# Sensor.net
KiCad netlist of a schematic drawn in Altium Designer
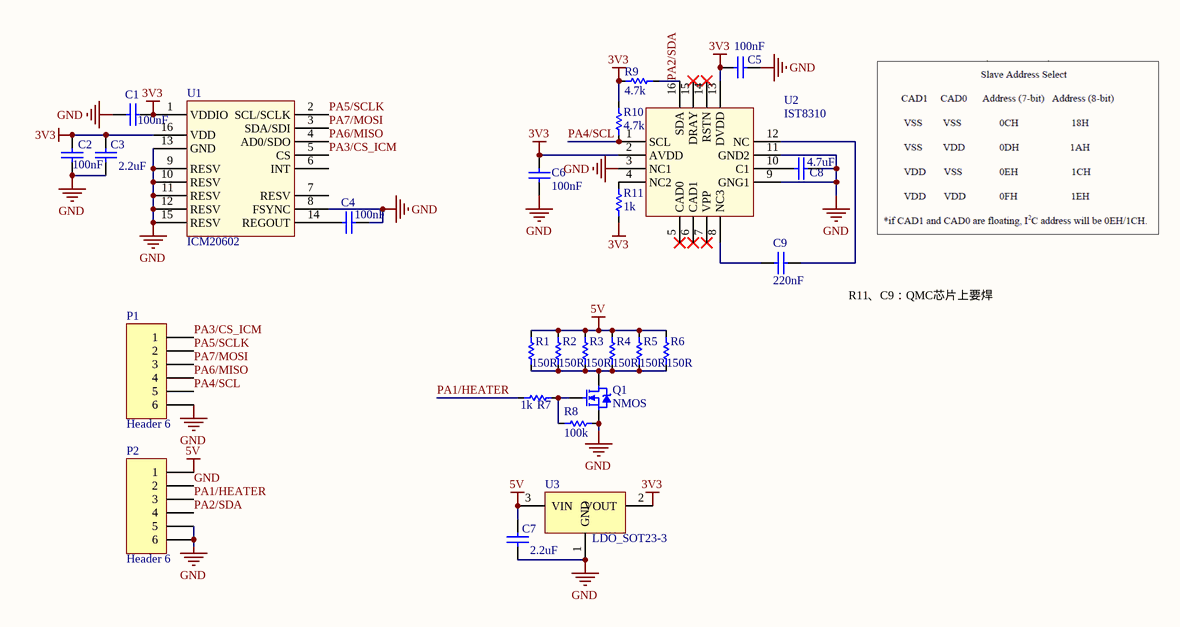
[diagram p0: Sensor.SchDoc]

(export (version "E")
  (design (tool "Eeschema 10.0.6"))
  (components
    (comp (ref "C1")
      (value "100nF")
      (footprint "0402C")
      (description "Capacitor")
      (fields (field (name "PUBLISHER") "Altium Limited"))
      (libsource (lib "") (part "Cap_1"))
    )
    (comp (ref "C2")
      (value "100nF")
      (footprint "0402C")
      (description "Capacitor")
      (fields (field (name "PUBLISHER") "Altium Limited"))
      (libsource (lib "") (part "Cap_1"))
    )
    (comp (ref "C3")
      (value "2.2uF")
      (footprint "0402C")
      (description "Capacitor")
      (fields (field (name "PUBLISHER") "Altium Limited"))
      (libsource (lib "") (part "Cap_1"))
    )
    (comp (ref "C4")
      (value "100nF")
      (footprint "0402C")
      (description "Capacitor")
      (fields (field (name "PUBLISHER") "Altium Limited"))
      (libsource (lib "") (part "Cap_1"))
    )
    (comp (ref "C5")
      (value "100nF")
      (footprint "0402C")
      (description "Capacitor")
      (fields (field (name "PUBLISHER") "Altium Limited"))
      (libsource (lib "MyComponents") (part "Cap"))
    )
    (comp (ref "C6")
      (value "100nF")
      (footprint "0402C")
      (description "Capacitor")
      (fields (field (name "PUBLISHER") "Altium Limited"))
      (libsource (lib "MyComponents_v2.4") (part "Cap"))
    )
    (comp (ref "C7")
      (value "2.2uF")
      (footprint "0402C")
      (description "Capacitor")
      (fields (field (name "PUBLISHER") "Altium Limited"))
      (libsource (lib "") (part "Cap_1"))
    )
    (comp (ref "C8")
      (value "4.7uF")
      (footprint "0402C")
      (description "Capacitor")
      (fields (field (name "PUBLISHER") "Altium Limited"))
      (libsource (lib "MyComponents_v2.4") (part "Cap"))
    )
    (comp (ref "C9")
      (value "220nF")
      (footprint "0402C")
      (description "Capacitor")
      (fields (field (name "PUBLISHER") "Altium Limited"))
      (libsource (lib "MyComponents_v2.5") (part "Cap"))
    )
    (comp (ref "P1")
      (value "Header 6")
      (footprint "HEADER 6x1 _ 1.0mm")
      (description "Header, 5-Pin")
      (fields (field (name "PUBLISHER") "Altium Limited"))
      (libsource (lib "MyComponents_v2.5") (part "Header 6"))
    )
    (comp (ref "P2")
      (value "Header 6")
      (footprint "HEADER 6x1 _ 1.0mm")
      (description "Header, 5-Pin")
      (fields (field (name "PUBLISHER") "Altium Limited"))
      (libsource (lib "MyComponents_v2.5") (part "Header 6"))
    )
    (comp (ref "Q1")
      (value "NMOS")
      (footprint "SOT-23-3")
      (description "N-Channel Power MOSFET")
      (fields (field (name "PUBLISHER") "Altium Limited"))
      (libsource (lib "MyComponents_v2.5") (part "NMOS(SOT23)"))
    )
    (comp (ref "R1")
      (value "150R")
      (footprint "0603R")
      (description "Resistor")
      (fields (field (name "PUBLISHER") "Altium Limited"))
      (libsource (lib "MyComponents_v2.5") (part "Res1"))
    )
    (comp (ref "R2")
      (value "150R")
      (footprint "0603R")
      (description "Resistor")
      (fields (field (name "PUBLISHER") "Altium Limited"))
      (libsource (lib "MyComponents_v2.5") (part "Res1"))
    )
    (comp (ref "R3")
      (value "150R")
      (footprint "0603R")
      (description "Resistor")
      (fields (field (name "PUBLISHER") "Altium Limited"))
      (libsource (lib "MyComponents_v2.5") (part "Res1"))
    )
    (comp (ref "R4")
      (value "150R")
      (footprint "0603R")
      (description "Resistor")
      (fields (field (name "PUBLISHER") "Altium Limited"))
      (libsource (lib "MyComponents_v2.5") (part "Res1"))
    )
    (comp (ref "R5")
      (value "150R")
      (footprint "0603R")
      (description "Resistor")
      (fields (field (name "PUBLISHER") "Altium Limited"))
      (libsource (lib "MyComponents_v2.5") (part "Res1"))
    )
    (comp (ref "R6")
      (value "150R")
      (footprint "0603R")
      (description "Resistor")
      (fields (field (name "PUBLISHER") "Altium Limited"))
      (libsource (lib "MyComponents_v2.5") (part "Res1"))
    )
    (comp (ref "R7")
      (value "1k")
      (footprint "0402R")
      (description "Resistor")
      (fields (field (name "PUBLISHER") "Altium Limited"))
      (libsource (lib "MyComponents_v2.5") (part "Res1"))
    )
    (comp (ref "R8")
      (value "100k")
      (footprint "0402R")
      (description "Resistor")
      (fields (field (name "PUBLISHER") "Altium Limited"))
      (libsource (lib "MyComponents_v2.5") (part "Res1"))
    )
    (comp (ref "R9")
      (value "4.7k")
      (footprint "0402R")
      (description "Resistor")
      (fields (field (name "PUBLISHER") "Altium Limited"))
      (libsource (lib "MyComponents_v2.4") (part "Res1"))
    )
    (comp (ref "R10")
      (value "4.7k")
      (footprint "0402R")
      (description "Resistor")
      (fields (field (name "PUBLISHER") "Altium Limited"))
      (libsource (lib "MyComponents_v2.4") (part "Res1"))
    )
    (comp (ref "R11")
      (value "1k")
      (footprint "0402R")
      (description "Resistor")
      (fields (field (name "PUBLISHER") "Altium Limited"))
      (libsource (lib "MyComponents_v2.4") (part "Res1"))
    )
    (comp (ref "U1")
      (value "ICM20602")
      (footprint "LGA-16")
      (libsource (lib "MyComponents_v2.5") (part "ICM20602"))
    )
    (comp (ref "U2")
      (value "IST8310")
      (footprint "LGA16")
      (libsource (lib "MyComponents_v2.5") (part "IST8310"))
    )
    (comp (ref "U3")
      (value "LDO_SOT23-3")
      (footprint "SOT-23-3")
      (libsource (lib "MyComponents_v2.5") (part "LDO_SOT23-3"))
    )
  )
  (nets
    (net (code "1") (name "/PA1{slash}HEATER") (class "Default")
      (node (ref "P2") (pin "3") (pinfunction "3_3") (pintype "passive"))
      (node (ref "R7") (pin "1") (pinfunction "1_1") (pintype "passive"))
    )
    (net (code "2") (name "/PA2{slash}SDA") (class "Default")
      (node (ref "P2") (pin "4") (pinfunction "4_4") (pintype "passive"))
      (node (ref "R9") (pin "1") (pinfunction "1_1") (pintype "passive"))
      (node (ref "U2") (pin "16") (pinfunction "SDA_16") (pintype "passive"))
    )
    (net (code "3") (name "/PA3{slash}CS_ICM") (class "Default")
      (node (ref "P1") (pin "1") (pinfunction "1_1") (pintype "passive"))
      (node (ref "U1") (pin "5") (pinfunction "CS_5") (pintype "passive"))
    )
    (net (code "4") (name "/PA4{slash}SCL") (class "Default")
      (node (ref "P1") (pin "5") (pinfunction "5_5") (pintype "passive"))
      (node (ref "R10") (pin "1") (pinfunction "1_1") (pintype "passive"))
      (node (ref "U2") (pin "1") (pinfunction "SCL_1") (pintype "passive"))
    )
    (net (code "5") (name "/PA5{slash}SCLK") (class "Default")
      (node (ref "P1") (pin "2") (pinfunction "2_2") (pintype "passive"))
      (node (ref "U1") (pin "2") (pinfunction "SCL/SCLK_2") (pintype "passive"))
    )
    (net (code "6") (name "/PA6{slash}MISO") (class "Default")
      (node (ref "P1") (pin "4") (pinfunction "4_4") (pintype "passive"))
      (node (ref "U1") (pin "4") (pinfunction "AD0/SDO_4") (pintype "passive"))
    )
    (net (code "7") (name "/PA7{slash}MOSI") (class "Default")
      (node (ref "P1") (pin "3") (pinfunction "3_3") (pintype "passive"))
      (node (ref "U1") (pin "3") (pinfunction "SDA/SDI_3") (pintype "passive"))
    )
    (net (code "8") (name "3V3") (class "Default")
      (node (ref "C1") (pin "2") (pinfunction "2_2") (pintype "passive"))
      (node (ref "C2") (pin "2") (pinfunction "2_2") (pintype "passive"))
      (node (ref "C3") (pin "1") (pinfunction "1_1") (pintype "passive"))
      (node (ref "C5") (pin "2") (pinfunction "2_2") (pintype "passive"))
      (node (ref "C6") (pin "2") (pinfunction "2_2") (pintype "passive"))
      (node (ref "R10") (pin "2") (pinfunction "2_2") (pintype "passive"))
      (node (ref "R11") (pin "1") (pinfunction "1_1") (pintype "passive"))
      (node (ref "R9") (pin "2") (pinfunction "2_2") (pintype "passive"))
      (node (ref "U1") (pin "1") (pinfunction "VDDIO_1") (pintype "passive"))
      (node (ref "U1") (pin "16") (pinfunction "VDD_16") (pintype "passive"))
      (node (ref "U2") (pin "13") (pinfunction "DVDD_13") (pintype "passive"))
      (node (ref "U2") (pin "2") (pinfunction "AVDD_2") (pintype "passive"))
      (node (ref "U3") (pin "2") (pinfunction "VOUT_2") (pintype "passive"))
    )
    (net (code "9") (name "5V") (class "Default")
      (node (ref "C7") (pin "1") (pinfunction "1_1") (pintype "passive"))
      (node (ref "P2") (pin "1") (pinfunction "1_1") (pintype "passive"))
      (node (ref "R1") (pin "1") (pinfunction "1_1") (pintype "passive"))
      (node (ref "R2") (pin "1") (pinfunction "1_1") (pintype "passive"))
      (node (ref "R3") (pin "1") (pinfunction "1_1") (pintype "passive"))
      (node (ref "R4") (pin "2") (pinfunction "2_2") (pintype "passive"))
      (node (ref "R5") (pin "2") (pinfunction "2_2") (pintype "passive"))
      (node (ref "R6") (pin "2") (pinfunction "2_2") (pintype "passive"))
      (node (ref "U3") (pin "3") (pinfunction "VIN_3") (pintype "passive"))
    )
    (net (code "10") (name "GND") (class "Default")
      (node (ref "C1") (pin "1") (pinfunction "1_1") (pintype "passive"))
      (node (ref "C2") (pin "1") (pinfunction "1_1") (pintype "passive"))
      (node (ref "C3") (pin "2") (pinfunction "2_2") (pintype "passive"))
      (node (ref "C4") (pin "2") (pinfunction "2_2") (pintype "passive"))
      (node (ref "C5") (pin "1") (pinfunction "1_1") (pintype "passive"))
      (node (ref "C6") (pin "1") (pinfunction "1_1") (pintype "passive"))
      (node (ref "C7") (pin "2") (pinfunction "2_2") (pintype "passive"))
      (node (ref "C8") (pin "1") (pinfunction "1_1") (pintype "passive"))
      (node (ref "P1") (pin "6") (pinfunction "6_6") (pintype "passive"))
      (node (ref "P2") (pin "2") (pinfunction "2_2") (pintype "passive"))
      (node (ref "P2") (pin "5") (pinfunction "5_5") (pintype "passive"))
      (node (ref "P2") (pin "6") (pinfunction "6_6") (pintype "passive"))
      (node (ref "Q1") (pin "2") (pinfunction "S_2") (pintype "passive"))
      (node (ref "R8") (pin "2") (pinfunction "2_2") (pintype "passive"))
      (node (ref "U1") (pin "10") (pinfunction "RESV_10") (pintype "passive"))
      (node (ref "U1") (pin "11") (pinfunction "RESV_11") (pintype "passive"))
      (node (ref "U1") (pin "12") (pinfunction "RESV_12") (pintype "passive"))
      (node (ref "U1") (pin "13") (pinfunction "GND_13") (pintype "passive"))
      (node (ref "U1") (pin "15") (pinfunction "RESV_15") (pintype "passive"))
      (node (ref "U1") (pin "8") (pinfunction "FSYNC_8") (pintype "passive"))
      (node (ref "U1") (pin "9") (pinfunction "RESV_9") (pintype "passive"))
      (node (ref "U2") (pin "11") (pinfunction "GND2_11") (pintype "passive"))
      (node (ref "U2") (pin "3") (pinfunction "NC1_3") (pintype "passive"))
      (node (ref "U2") (pin "9") (pinfunction "GNG1_9") (pintype "passive"))
      (node (ref "U3") (pin "1") (pinfunction "GND_1") (pintype "passive"))
    )
    (net (code "11") (name "Net-(Q1-D)") (class "Default")
      (node (ref "Q1") (pin "3") (pinfunction "D_3") (pintype "passive"))
      (node (ref "R1") (pin "2") (pinfunction "2_2") (pintype "passive"))
      (node (ref "R2") (pin "2") (pinfunction "2_2") (pintype "passive"))
      (node (ref "R3") (pin "2") (pinfunction "2_2") (pintype "passive"))
      (node (ref "R4") (pin "1") (pinfunction "1_1") (pintype "passive"))
      (node (ref "R5") (pin "1") (pinfunction "1_1") (pintype "passive"))
      (node (ref "R6") (pin "1") (pinfunction "1_1") (pintype "passive"))
    )
    (net (code "12") (name "Net-(Q1-G)") (class "Default")
      (node (ref "Q1") (pin "1") (pinfunction "G_1") (pintype "passive"))
      (node (ref "R7") (pin "2") (pinfunction "2_2") (pintype "passive"))
      (node (ref "R8") (pin "1") (pinfunction "1_1") (pintype "passive"))
    )
    (net (code "13") (name "Net-(U1-REGOUT)") (class "Default")
      (node (ref "C4") (pin "1") (pinfunction "1_1") (pintype "passive"))
      (node (ref "U1") (pin "14") (pinfunction "REGOUT_14") (pintype "passive"))
    )
    (net (code "14") (name "Net-(U2-C1)") (class "Default")
      (node (ref "C8") (pin "2") (pinfunction "2_2") (pintype "passive"))
      (node (ref "U2") (pin "10") (pinfunction "C1_10") (pintype "passive"))
    )
    (net (code "15") (name "Net-(U2-NC)") (class "Default")
      (node (ref "C9") (pin "2") (pinfunction "2_2") (pintype "passive"))
      (node (ref "U2") (pin "12") (pinfunction "NC_12") (pintype "passive"))
    )
    (net (code "16") (name "Net-(U2-NC2)") (class "Default")
      (node (ref "R11") (pin "2") (pinfunction "2_2") (pintype "passive"))
      (node (ref "U2") (pin "4") (pinfunction "NC2_4") (pintype "passive"))
    )
    (net (code "17") (name "Net-(U2-NC3)") (class "Default")
      (node (ref "C9") (pin "1") (pinfunction "1_1") (pintype "passive"))
      (node (ref "U2") (pin "8") (pinfunction "NC3_8") (pintype "passive"))
    )
    (net (code "18") (name "unconnected-(U1-INT-Pad6)") (class "Default")
      (node (ref "U1") (pin "6") (pinfunction "INT_6") (pintype "passive"))
    )
    (net (code "19") (name "unconnected-(U1-RESV-Pad7)") (class "Default")
      (node (ref "U1") (pin "7") (pinfunction "RESV_7") (pintype "passive"))
    )
    (net (code "20") (name "unconnected-(U2-CAD0-Pad5)") (class "Default")
      (node (ref "U2") (pin "5") (pinfunction "CAD0_5") (pintype "passive+no_connect"))
    )
    (net (code "21") (name "unconnected-(U2-CAD1-Pad6)") (class "Default")
      (node (ref "U2") (pin "6") (pinfunction "CAD1_6") (pintype "passive+no_connect"))
    )
    (net (code "22") (name "unconnected-(U2-DRAY-Pad15)") (class "Default")
      (node (ref "U2") (pin "15") (pinfunction "DRAY_15") (pintype "passive+no_connect"))
    )
    (net (code "23") (name "unconnected-(U2-RSTN-Pad14)") (class "Default")
      (node (ref "U2") (pin "14") (pinfunction "RSTN_14") (pintype "passive+no_connect"))
    )
    (net (code "24") (name "unconnected-(U2-VPP-Pad7)") (class "Default")
      (node (ref "U2") (pin "7") (pinfunction "VPP_7") (pintype "passive+no_connect"))
    )
  )
)
